# SCH_usb-hub_2024-10-17.net
KiCad netlist of a schematic drawn in EasyEDA
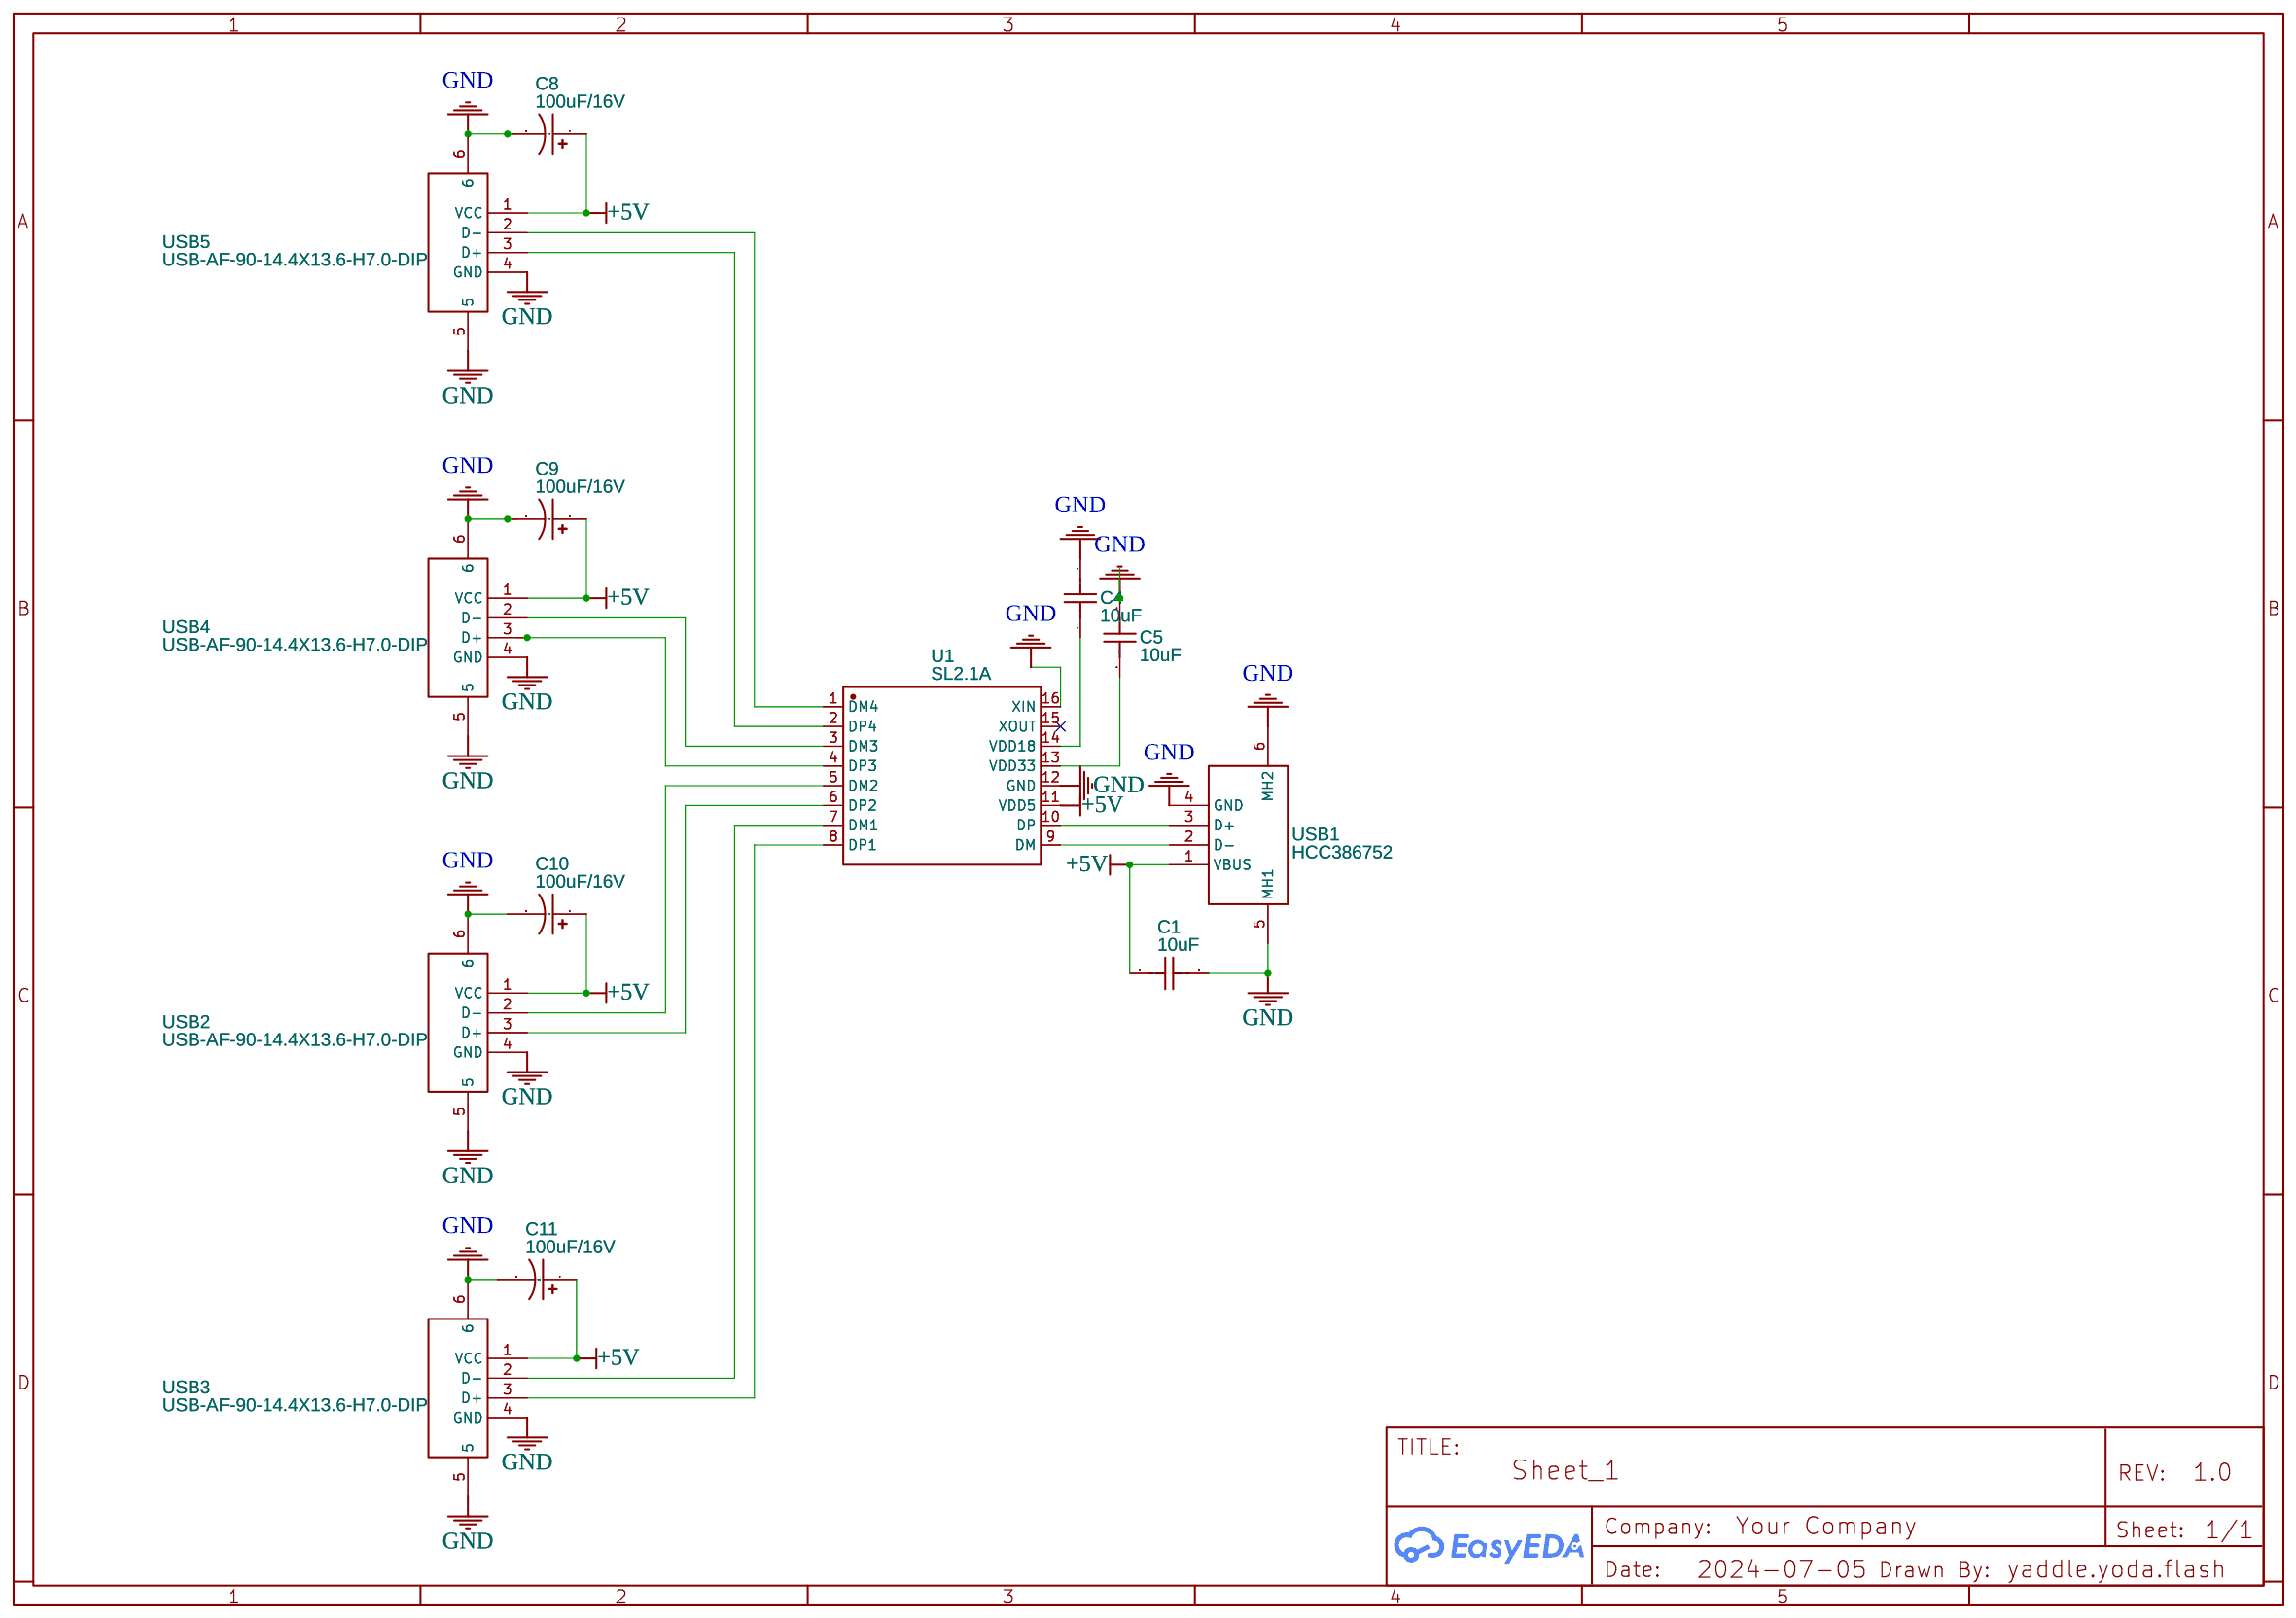
[diagram p0: Horizontal_USB]
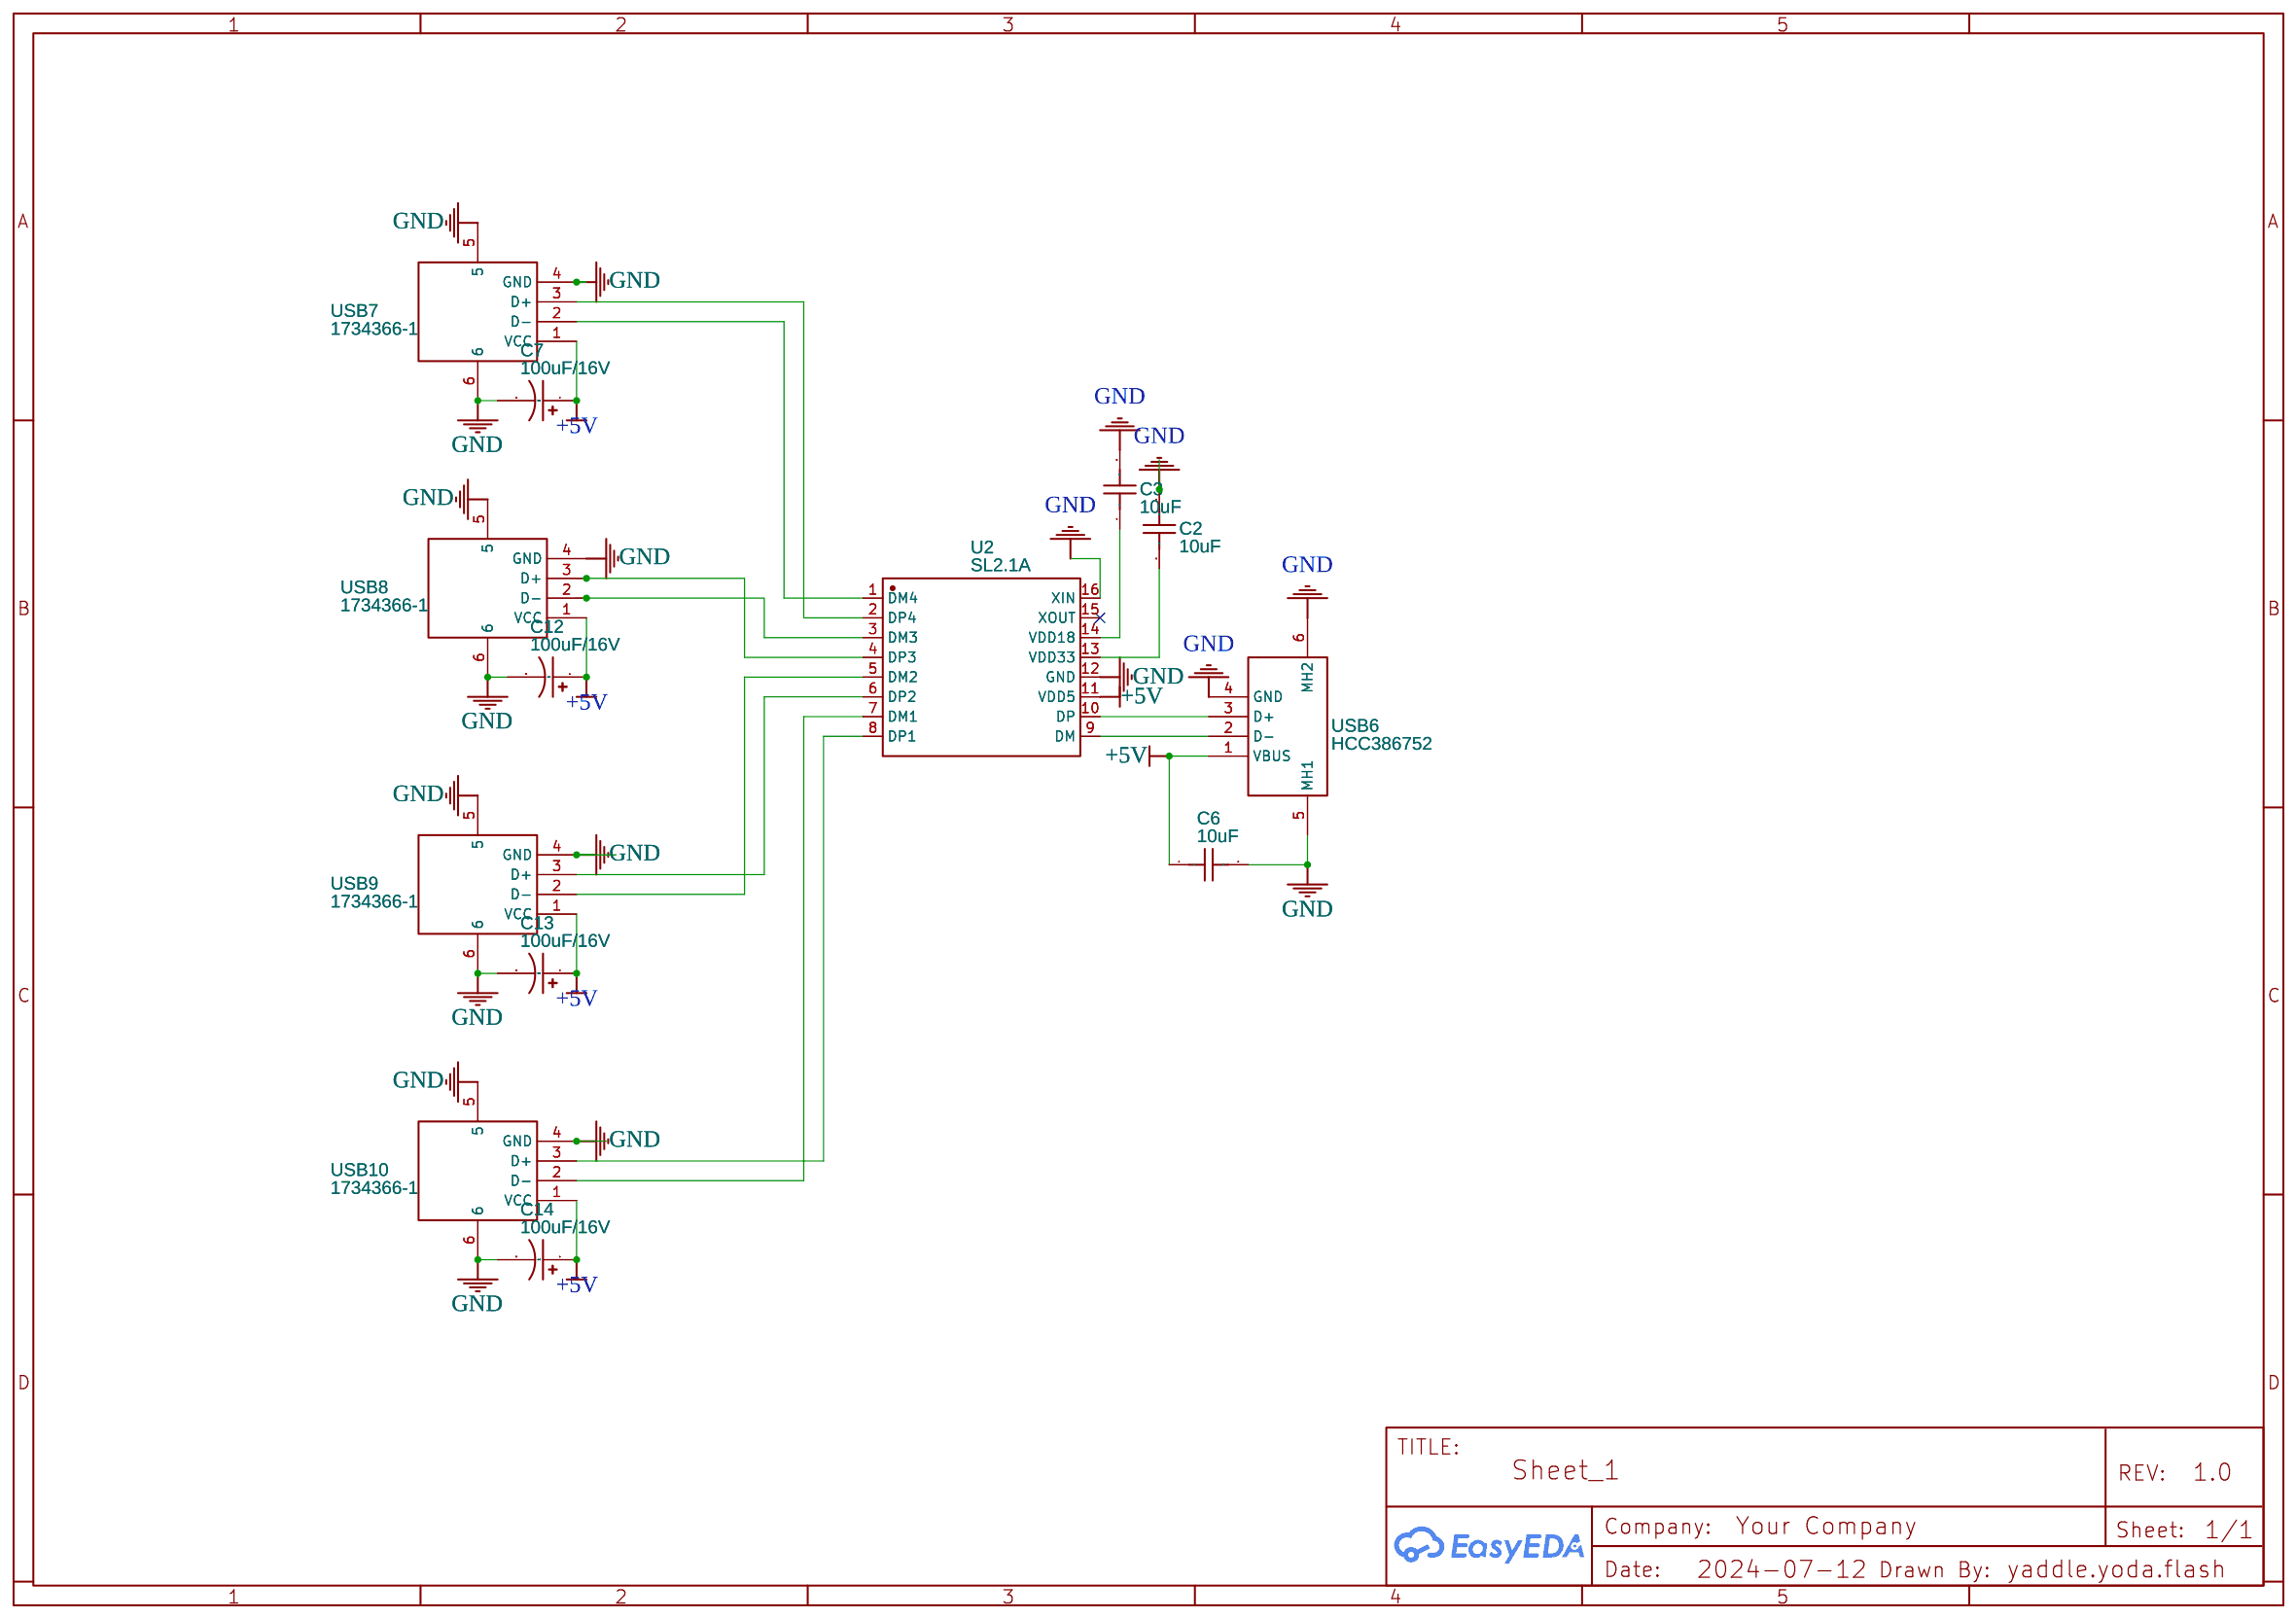
[diagram p1: Vertical_USB]

(export (version "E")
  (design (tool "Eeschema 10.0.6"))
  (components
    (comp (ref "C1")
      (value "10uF")
      (fields
        (field (name "Manufacturer Part") "CL10A106KP8NNNC")
        (field (name "Manufacturer") "SAMSUNG(三星)")
      )
      (libsource (lib "") (part "CL10A106KP8NNNC_1"))
    )
    (comp (ref "C4")
      (value "10uF")
      (fields
        (field (name "Manufacturer Part") "CL10A106KP8NNNC")
        (field (name "Manufacturer") "SAMSUNG(三星)")
      )
      (libsource (lib "") (part "CL10A106KP8NNNC"))
    )
    (comp (ref "C5")
      (value "10uF")
      (fields
        (field (name "Manufacturer Part") "CL10A106KP8NNNC")
        (field (name "Manufacturer") "SAMSUNG(三星)")
      )
      (libsource (lib "") (part "CL10A106KP8NNNC_2"))
    )
    (comp (ref "C8") (value "100uF/16V") (libsource (lib "") (part "C_Tan_SMD_A_US")))
    (comp (ref "C9") (value "100uF/16V") (libsource (lib "") (part "C_Tan_SMD_A_US")))
    (comp (ref "C10") (value "100uF/16V") (libsource (lib "") (part "C_Tan_SMD_A_US")))
    (comp (ref "C11") (value "100uF/16V") (libsource (lib "") (part "C_Tan_SMD_A_US_1")))
    (comp (ref "U1")
      (value "SL2.1A")
      (fields (field (name "Manufacturer") "CoreChips(和芯润德)"))
      (libsource (lib "") (part "SL2.1A"))
    )
    (comp (ref "USB1")
      (value "HCC386752")
      (fields (field (name "Manufacturer Part") "U-USBAR04P-M003") (field (name "Manufacturer") "Ckmtw(灿科盟)"))
      (libsource (lib "") (part "HCC386752"))
    )
    (comp (ref "USB2")
      (value "USB-AF-90-14.4X13.6-H7.0-DIP")
      (fields (field (name "Manufacturer Part") "903-131A1011D10100") (field (name "Manufacturer") "精拓金"))
      (libsource (lib "") (part "USB-AF-90-14.4X13.6-H7.0-DIP"))
    )
    (comp (ref "USB3")
      (value "USB-AF-90-14.4X13.6-H7.0-DIP")
      (fields (field (name "Manufacturer Part") "903-131A1011D10100") (field (name "Manufacturer") "精拓金"))
      (libsource (lib "") (part "USB-AF-90-14.4X13.6-H7.0-DIP"))
    )
    (comp (ref "USB4")
      (value "USB-AF-90-14.4X13.6-H7.0-DIP")
      (fields (field (name "Manufacturer Part") "903-131A1011D10100") (field (name "Manufacturer") "精拓金"))
      (libsource (lib "") (part "USB-AF-90-14.4X13.6-H7.0-DIP"))
    )
    (comp (ref "USB5")
      (value "USB-AF-90-14.4X13.6-H7.0-DIP")
      (fields (field (name "Manufacturer Part") "903-131A1011D10100") (field (name "Manufacturer") "精拓金"))
      (libsource (lib "") (part "USB-AF-90-14.4X13.6-H7.0-DIP"))
    )
    (comp (ref "C2")
      (value "10uF")
      (fields
        (field (name "Manufacturer Part") "CL10A106KP8NNNC")
        (field (name "Manufacturer") "SAMSUNG(三星)")
      )
      (libsource (lib "") (part "CL10A106KP8NNNC_1"))
    )
    (comp (ref "C3")
      (value "10uF")
      (fields
        (field (name "Manufacturer Part") "CL10A106KP8NNNC")
        (field (name "Manufacturer") "SAMSUNG(三星)")
      )
      (libsource (lib "") (part "CL10A106KP8NNNC_2"))
    )
    (comp (ref "C6")
      (value "10uF")
      (fields
        (field (name "Manufacturer Part") "CL10A106KP8NNNC")
        (field (name "Manufacturer") "SAMSUNG(三星)")
      )
      (libsource (lib "") (part "CL10A106KP8NNNC"))
    )
    (comp (ref "C7") (value "100uF/16V") (libsource (lib "") (part "C_Tan_SMD_A_US")))
    (comp (ref "C12") (value "100uF/16V") (libsource (lib "") (part "C_Tan_SMD_A_US")))
    (comp (ref "C13") (value "100uF/16V") (libsource (lib "") (part "C_Tan_SMD_A_US")))
    (comp (ref "C14") (value "100uF/16V") (libsource (lib "") (part "C_Tan_SMD_A_US_1")))
    (comp (ref "U2")
      (value "SL2.1A")
      (fields (field (name "Manufacturer") "CoreChips(和芯润德)"))
      (libsource (lib "") (part "SL2.1A"))
    )
    (comp (ref "USB6")
      (value "HCC386752")
      (fields (field (name "Manufacturer Part") "U-USBAR04P-M003") (field (name "Manufacturer") "Ckmtw(灿科盟)"))
      (libsource (lib "") (part "HCC386752"))
    )
    (comp (ref "USB7")
      (value "1734366-1")
      (fields (field (name "Manufacturer") "TE Connectivity(泰科电子)"))
      (libsource (lib "") (part "1734366-1"))
    )
    (comp (ref "USB8")
      (value "1734366-1")
      (fields (field (name "Manufacturer") "TE Connectivity(泰科电子)"))
      (libsource (lib "") (part "1734366-1"))
    )
    (comp (ref "USB9")
      (value "1734366-1")
      (fields (field (name "Manufacturer") "TE Connectivity(泰科电子)"))
      (libsource (lib "") (part "1734366-1"))
    )
    (comp (ref "USB10")
      (value "1734366-1")
      (fields (field (name "Manufacturer") "TE Connectivity(泰科电子)"))
      (libsource (lib "") (part "1734366-1"))
    )
  )
  (nets
    (net (code "1") (name "+5V") (class "Default")
      (node (ref "C1") (pin "1") (pinfunction "1_1") (pintype "unspecified"))
      (node (ref "C10") (pin "1") (pinfunction "1_1") (pintype "unspecified"))
      (node (ref "C11") (pin "1") (pinfunction "1_1") (pintype "unspecified"))
      (node (ref "C12") (pin "1") (pinfunction "1_1") (pintype "unspecified"))
      (node (ref "C13") (pin "1") (pinfunction "1_1") (pintype "unspecified"))
      (node (ref "C14") (pin "1") (pinfunction "1_1") (pintype "unspecified"))
      (node (ref "C6") (pin "1") (pinfunction "1_1") (pintype "unspecified"))
      (node (ref "C7") (pin "1") (pinfunction "1_1") (pintype "unspecified"))
      (node (ref "C8") (pin "1") (pinfunction "1_1") (pintype "unspecified"))
      (node (ref "C9") (pin "1") (pinfunction "1_1") (pintype "unspecified"))
      (node (ref "U1") (pin "11") (pinfunction "VDD5_11") (pintype "unspecified"))
      (node (ref "U2") (pin "11") (pinfunction "VDD5_11") (pintype "unspecified"))
      (node (ref "USB1") (pin "1") (pinfunction "VBUS_1") (pintype "unspecified"))
      (node (ref "USB10") (pin "1") (pinfunction "VCC_1") (pintype "unspecified"))
      (node (ref "USB2") (pin "1") (pinfunction "VCC_1") (pintype "unspecified"))
      (node (ref "USB3") (pin "1") (pinfunction "VCC_1") (pintype "unspecified"))
      (node (ref "USB4") (pin "1") (pinfunction "VCC_1") (pintype "unspecified"))
      (node (ref "USB5") (pin "1") (pinfunction "VCC_1") (pintype "unspecified"))
      (node (ref "USB6") (pin "1") (pinfunction "VBUS_1") (pintype "unspecified"))
      (node (ref "USB7") (pin "1") (pinfunction "VCC_1") (pintype "unspecified"))
      (node (ref "USB8") (pin "1") (pinfunction "VCC_1") (pintype "unspecified"))
      (node (ref "USB9") (pin "1") (pinfunction "VCC_1") (pintype "unspecified"))
    )
    (net (code "2") (name "GND") (class "Default")
      (node (ref "C1") (pin "2") (pinfunction "2_2") (pintype "unspecified"))
      (node (ref "C10") (pin "2") (pinfunction "2_2") (pintype "unspecified"))
      (node (ref "C11") (pin "2") (pinfunction "2_2") (pintype "unspecified"))
      (node (ref "C12") (pin "2") (pinfunction "2_2") (pintype "unspecified"))
      (node (ref "C13") (pin "2") (pinfunction "2_2") (pintype "unspecified"))
      (node (ref "C14") (pin "2") (pinfunction "2_2") (pintype "unspecified"))
      (node (ref "C2") (pin "1") (pinfunction "1_1") (pintype "unspecified"))
      (node (ref "C3") (pin "2") (pinfunction "2_2") (pintype "unspecified"))
      (node (ref "C4") (pin "2") (pinfunction "2_2") (pintype "unspecified"))
      (node (ref "C5") (pin "1") (pinfunction "1_1") (pintype "unspecified"))
      (node (ref "C6") (pin "2") (pinfunction "2_2") (pintype "unspecified"))
      (node (ref "C7") (pin "2") (pinfunction "2_2") (pintype "unspecified"))
      (node (ref "C8") (pin "2") (pinfunction "2_2") (pintype "unspecified"))
      (node (ref "C9") (pin "2") (pinfunction "2_2") (pintype "unspecified"))
      (node (ref "U1") (pin "12") (pinfunction "GND_12") (pintype "unspecified"))
      (node (ref "U1") (pin "16") (pinfunction "XIN_16") (pintype "unspecified"))
      (node (ref "U2") (pin "12") (pinfunction "GND_12") (pintype "unspecified"))
      (node (ref "U2") (pin "16") (pinfunction "XIN_16") (pintype "unspecified"))
      (node (ref "USB1") (pin "4") (pinfunction "GND_4") (pintype "unspecified"))
      (node (ref "USB1") (pin "5") (pinfunction "MH1_5") (pintype "unspecified"))
      (node (ref "USB1") (pin "6") (pinfunction "MH2_6") (pintype "unspecified"))
      (node (ref "USB10") (pin "4") (pinfunction "GND_4") (pintype "unspecified"))
      (node (ref "USB10") (pin "5") (pinfunction "5_5") (pintype "unspecified"))
      (node (ref "USB10") (pin "6") (pinfunction "6_6") (pintype "unspecified"))
      (node (ref "USB2") (pin "4") (pinfunction "GND_4") (pintype "unspecified"))
      (node (ref "USB2") (pin "5") (pinfunction "5_5") (pintype "unspecified"))
      (node (ref "USB2") (pin "6") (pinfunction "6_6") (pintype "unspecified"))
      (node (ref "USB3") (pin "4") (pinfunction "GND_4") (pintype "unspecified"))
      (node (ref "USB3") (pin "5") (pinfunction "5_5") (pintype "unspecified"))
      (node (ref "USB3") (pin "6") (pinfunction "6_6") (pintype "unspecified"))
      (node (ref "USB4") (pin "4") (pinfunction "GND_4") (pintype "unspecified"))
      (node (ref "USB4") (pin "5") (pinfunction "5_5") (pintype "unspecified"))
      (node (ref "USB4") (pin "6") (pinfunction "6_6") (pintype "unspecified"))
      (node (ref "USB5") (pin "4") (pinfunction "GND_4") (pintype "unspecified"))
      (node (ref "USB5") (pin "5") (pinfunction "5_5") (pintype "unspecified"))
      (node (ref "USB5") (pin "6") (pinfunction "6_6") (pintype "unspecified"))
      (node (ref "USB6") (pin "4") (pinfunction "GND_4") (pintype "unspecified"))
      (node (ref "USB6") (pin "5") (pinfunction "MH1_5") (pintype "unspecified"))
      (node (ref "USB6") (pin "6") (pinfunction "MH2_6") (pintype "unspecified"))
      (node (ref "USB7") (pin "4") (pinfunction "GND_4") (pintype "unspecified"))
      (node (ref "USB7") (pin "5") (pinfunction "5_5") (pintype "unspecified"))
      (node (ref "USB7") (pin "6") (pinfunction "6_6") (pintype "unspecified"))
      (node (ref "USB8") (pin "4") (pinfunction "GND_4") (pintype "unspecified"))
      (node (ref "USB8") (pin "5") (pinfunction "5_5") (pintype "unspecified"))
      (node (ref "USB8") (pin "6") (pinfunction "6_6") (pintype "unspecified"))
      (node (ref "USB9") (pin "4") (pinfunction "GND_4") (pintype "unspecified"))
      (node (ref "USB9") (pin "5") (pinfunction "5_5") (pintype "unspecified"))
      (node (ref "USB9") (pin "6") (pinfunction "6_6") (pintype "unspecified"))
    )
    (net (code "3") (name "Net-(U1-DM)") (class "Default")
      (node (ref "U1") (pin "9") (pinfunction "DM_9") (pintype "unspecified"))
      (node (ref "USB1") (pin "2") (pinfunction "D-_2") (pintype "unspecified"))
    )
    (net (code "4") (name "Net-(U1-DM1)") (class "Default")
      (node (ref "U1") (pin "7") (pinfunction "DM1_7") (pintype "unspecified"))
      (node (ref "USB3") (pin "2") (pinfunction "D-_2") (pintype "unspecified"))
    )
    (net (code "5") (name "Net-(U1-DM2)") (class "Default")
      (node (ref "U1") (pin "5") (pinfunction "DM2_5") (pintype "unspecified"))
      (node (ref "USB2") (pin "2") (pinfunction "D-_2") (pintype "unspecified"))
    )
    (net (code "6") (name "Net-(U1-DM3)") (class "Default")
      (node (ref "U1") (pin "3") (pinfunction "DM3_3") (pintype "unspecified"))
      (node (ref "USB4") (pin "2") (pinfunction "D-_2") (pintype "unspecified"))
    )
    (net (code "7") (name "Net-(U1-DM4)") (class "Default")
      (node (ref "U1") (pin "1") (pinfunction "DM4_1") (pintype "unspecified"))
      (node (ref "USB5") (pin "2") (pinfunction "D-_2") (pintype "unspecified"))
    )
    (net (code "8") (name "Net-(U1-DP)") (class "Default")
      (node (ref "U1") (pin "10") (pinfunction "DP_10") (pintype "unspecified"))
      (node (ref "USB1") (pin "3") (pinfunction "D+_3") (pintype "unspecified"))
    )
    (net (code "9") (name "Net-(U1-DP1)") (class "Default")
      (node (ref "U1") (pin "8") (pinfunction "DP1_8") (pintype "unspecified"))
      (node (ref "USB3") (pin "3") (pinfunction "D+_3") (pintype "unspecified"))
    )
    (net (code "10") (name "Net-(U1-DP2)") (class "Default")
      (node (ref "U1") (pin "6") (pinfunction "DP2_6") (pintype "unspecified"))
      (node (ref "USB2") (pin "3") (pinfunction "D+_3") (pintype "unspecified"))
    )
    (net (code "11") (name "Net-(U1-DP3)") (class "Default")
      (node (ref "U1") (pin "4") (pinfunction "DP3_4") (pintype "unspecified"))
      (node (ref "USB4") (pin "3") (pinfunction "D+_3") (pintype "unspecified"))
    )
    (net (code "12") (name "Net-(U1-DP4)") (class "Default")
      (node (ref "U1") (pin "2") (pinfunction "DP4_2") (pintype "unspecified"))
      (node (ref "USB5") (pin "3") (pinfunction "D+_3") (pintype "unspecified"))
    )
    (net (code "13") (name "Net-(U1-VDD18)") (class "Default")
      (node (ref "C4") (pin "1") (pinfunction "1_1") (pintype "unspecified"))
      (node (ref "U1") (pin "14") (pinfunction "VDD18_14") (pintype "unspecified"))
    )
    (net (code "14") (name "Net-(U1-VDD33)") (class "Default")
      (node (ref "C5") (pin "2") (pinfunction "2_2") (pintype "unspecified"))
      (node (ref "U1") (pin "13") (pinfunction "VDD33_13") (pintype "unspecified"))
    )
    (net (code "15") (name "Net-(U2-DM)") (class "Default")
      (node (ref "U2") (pin "9") (pinfunction "DM_9") (pintype "unspecified"))
      (node (ref "USB6") (pin "2") (pinfunction "D-_2") (pintype "unspecified"))
    )
    (net (code "16") (name "Net-(U2-DM1)") (class "Default")
      (node (ref "U2") (pin "7") (pinfunction "DM1_7") (pintype "unspecified"))
      (node (ref "USB10") (pin "2") (pinfunction "D-_2") (pintype "unspecified"))
    )
    (net (code "17") (name "Net-(U2-DM2)") (class "Default")
      (node (ref "U2") (pin "5") (pinfunction "DM2_5") (pintype "unspecified"))
      (node (ref "USB9") (pin "2") (pinfunction "D-_2") (pintype "unspecified"))
    )
    (net (code "18") (name "Net-(U2-DM3)") (class "Default")
      (node (ref "U2") (pin "3") (pinfunction "DM3_3") (pintype "unspecified"))
      (node (ref "USB8") (pin "2") (pinfunction "D-_2") (pintype "unspecified"))
    )
    (net (code "19") (name "Net-(U2-DM4)") (class "Default")
      (node (ref "U2") (pin "1") (pinfunction "DM4_1") (pintype "unspecified"))
      (node (ref "USB7") (pin "2") (pinfunction "D-_2") (pintype "unspecified"))
    )
    (net (code "20") (name "Net-(U2-DP)") (class "Default")
      (node (ref "U2") (pin "10") (pinfunction "DP_10") (pintype "unspecified"))
      (node (ref "USB6") (pin "3") (pinfunction "D+_3") (pintype "unspecified"))
    )
    (net (code "21") (name "Net-(U2-DP1)") (class "Default")
      (node (ref "U2") (pin "8") (pinfunction "DP1_8") (pintype "unspecified"))
      (node (ref "USB10") (pin "3") (pinfunction "D+_3") (pintype "unspecified"))
    )
    (net (code "22") (name "Net-(U2-DP2)") (class "Default")
      (node (ref "U2") (pin "6") (pinfunction "DP2_6") (pintype "unspecified"))
      (node (ref "USB9") (pin "3") (pinfunction "D+_3") (pintype "unspecified"))
    )
    (net (code "23") (name "Net-(U2-DP3)") (class "Default")
      (node (ref "U2") (pin "4") (pinfunction "DP3_4") (pintype "unspecified"))
      (node (ref "USB8") (pin "3") (pinfunction "D+_3") (pintype "unspecified"))
    )
    (net (code "24") (name "Net-(U2-DP4)") (class "Default")
      (node (ref "U2") (pin "2") (pinfunction "DP4_2") (pintype "unspecified"))
      (node (ref "USB7") (pin "3") (pinfunction "D+_3") (pintype "unspecified"))
    )
    (net (code "25") (name "Net-(U2-VDD18)") (class "Default")
      (node (ref "C3") (pin "1") (pinfunction "1_1") (pintype "unspecified"))
      (node (ref "U2") (pin "14") (pinfunction "VDD18_14") (pintype "unspecified"))
    )
    (net (code "26") (name "Net-(U2-VDD33)") (class "Default")
      (node (ref "C2") (pin "2") (pinfunction "2_2") (pintype "unspecified"))
      (node (ref "U2") (pin "13") (pinfunction "VDD33_13") (pintype "unspecified"))
    )
    (net (code "27") (name "unconnected-(U1-XOUT-Pad15)") (class "Default")
      (node (ref "U1") (pin "15") (pinfunction "XOUT_15") (pintype "unspecified+no_connect"))
    )
    (net (code "28") (name "unconnected-(U2-XOUT-Pad15)") (class "Default")
      (node (ref "U2") (pin "15") (pinfunction "XOUT_15") (pintype "unspecified+no_connect"))
    )
  )
)
